# other.net
KiCad netlist of a schematic drawn in Altium Designer
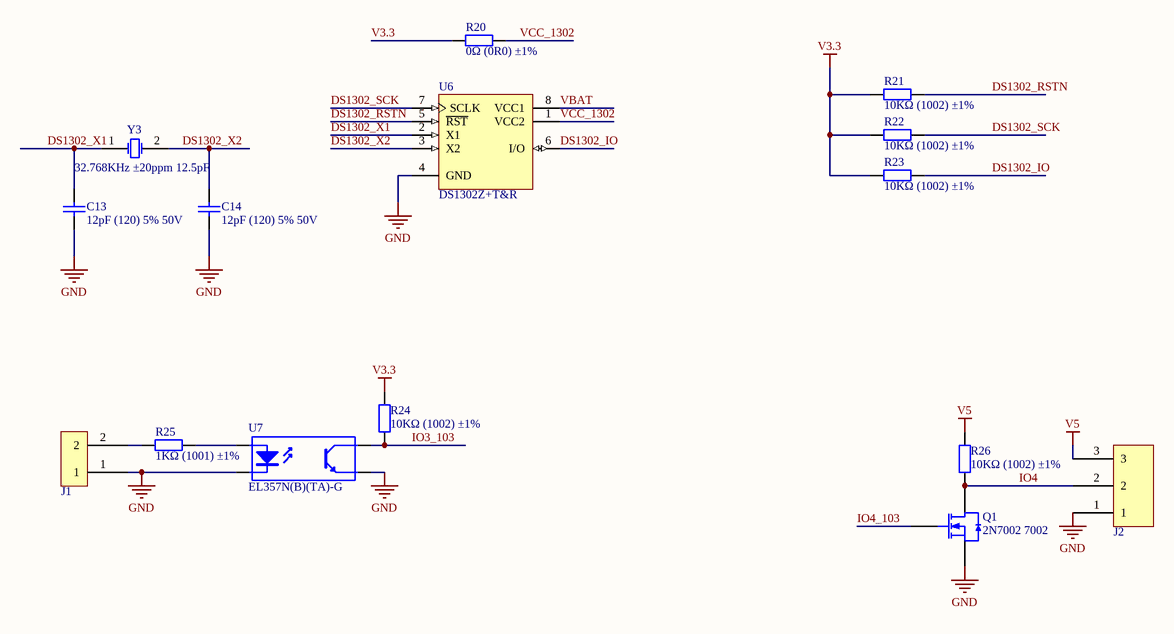
[diagram p0: other.SchDoc]

(export (version "E")
  (design (tool "Eeschema 10.0.6"))
  (components
    (comp (ref "C13")
      (value "12pF (120) 5% 50V")
      (footprint "0603_C")
      (description "贴片电容")
      (libsource (lib "Miscellaneous Devices LC") (part "0603 12pF (120) 5% 50V"))
    )
    (comp (ref "C14")
      (value "12pF (120) 5% 50V")
      (footprint "0603_C")
      (description "贴片电容")
      (libsource (lib "Miscellaneous Devices LC") (part "0603 12pF (120) 5% 50V"))
    )
    (comp (ref "J1") (value "KF301-2P") (footprint "KF301-2P") (libsource (lib "CHK-I") (part "KF301-2P")))
    (comp (ref "J2") (value "KF301-3P") (footprint "KF301-3P") (libsource (lib "CHK-I") (part "KF301-3P")))
    (comp (ref "Q1")
      (value "2N7002 7002")
      (footprint "SOT-23(SOT-23-3)")
      (description "MOS(场效应管)")
      (libsource (lib "Miscellaneous Devices LC") (part "2N7002 7002"))
    )
    (comp (ref "R20")
      (value "0Ω (0R0) ±1%")
      (footprint "1206_R")
      (description "贴片电阻")
      (libsource (lib "Miscellaneous Devices LC") (part "1206 0Ω (0R0) 1%"))
    )
    (comp (ref "R21")
      (value "10KΩ (1002) ±1%")
      (footprint "0603_R")
      (description "贴片电阻")
      (libsource (lib "Miscellaneous Devices LC") (part "0603 10KΩ (1002) 1%"))
    )
    (comp (ref "R22")
      (value "10KΩ (1002) ±1%")
      (footprint "0603_R")
      (description "贴片电阻")
      (libsource (lib "Miscellaneous Devices LC") (part "0603 10KΩ (1002) 1%"))
    )
    (comp (ref "R23")
      (value "10KΩ (1002) ±1%")
      (footprint "0603_R")
      (description "贴片电阻")
      (libsource (lib "Miscellaneous Devices LC") (part "0603 10KΩ (1002) 1%"))
    )
    (comp (ref "R24")
      (value "10KΩ (1002) ±1%")
      (footprint "1206_R")
      (description "贴片电阻")
      (libsource (lib "Miscellaneous Devices LC") (part "1206 10KΩ (1002) 1%"))
    )
    (comp (ref "R25")
      (value "1KΩ (1001) ±1%")
      (footprint "1206_R")
      (description "贴片电阻")
      (libsource (lib "Miscellaneous Devices LC") (part "1206 1KΩ (1001) 1%"))
    )
    (comp (ref "R26")
      (value "10KΩ (1002) ±1%")
      (footprint "1206_R")
      (description "贴片电阻")
      (libsource (lib "Miscellaneous Devices LC") (part "1206 10KΩ (1002) 1%"))
    )
    (comp (ref "U6")
      (value "DS1302Z+T&R")
      (footprint "SOIC-8_150mil")
      (description "实时时钟")
      (libsource (lib "Miscellaneous Devices LC") (part "DS1302Z+T&R_[C8959]"))
    )
    (comp (ref "U7")
      (value "EL357N(B)(TA)-G")
      (footprint "SOP-4_P2.54")
      (description "贴片光耦")
      (libsource (lib "Miscellaneous Devices LC") (part "EL357N(B)(TA)-G_[C6649]"))
    )
    (comp (ref "Y3")
      (value "32.768KHz ±20ppm 12.5pF")
      (footprint "SMD-3215_2P FC - 135")
      (description "贴片晶振")
      (libsource (lib "Miscellaneous Devices LC") (part "SMD-3215_2P 32.768KHz 20ppm 12.5pF"))
    )
  )
  (nets
    (net (code "1") (name "/DS1302_IO") (class "Default")
      (node (ref "R23") (pin "2") (pinfunction "2_2") (pintype "passive"))
      (node (ref "U6") (pin "6") (pinfunction "I/O_6") (pintype "bidirectional"))
    )
    (net (code "2") (name "/DS1302_RSTN") (class "Default")
      (node (ref "R21") (pin "2") (pinfunction "2_2") (pintype "passive"))
      (node (ref "U6") (pin "5") (pinfunction "~{RST}_5") (pintype "input"))
    )
    (net (code "3") (name "/DS1302_SCK") (class "Default")
      (node (ref "R22") (pin "2") (pinfunction "2_2") (pintype "passive"))
      (node (ref "U6") (pin "7") (pinfunction "SCLK_7") (pintype "input"))
    )
    (net (code "4") (name "/DS1302_X1") (class "Default")
      (node (ref "C13") (pin "2") (pinfunction "2_2") (pintype "passive"))
      (node (ref "U6") (pin "2") (pinfunction "X1_2") (pintype "input"))
      (node (ref "Y3") (pin "1") (pinfunction "OSC1_1") (pintype "passive"))
    )
    (net (code "5") (name "/DS1302_X2") (class "Default")
      (node (ref "C14") (pin "2") (pinfunction "2_2") (pintype "passive"))
      (node (ref "U6") (pin "3") (pinfunction "X2_3") (pintype "input"))
      (node (ref "Y3") (pin "2") (pinfunction "OSC2_2") (pintype "passive"))
    )
    (net (code "6") (name "/IO3_103") (class "Default")
      (node (ref "R24") (pin "1") (pinfunction "1_1") (pintype "passive"))
      (node (ref "U7") (pin "4") (pinfunction "C_4") (pintype "passive"))
    )
    (net (code "7") (name "/IO4") (class "Default")
      (node (ref "J2") (pin "2") (pinfunction "2_2") (pintype "passive"))
      (node (ref "Q1") (pin "3") (pinfunction "D_3") (pintype "passive"))
      (node (ref "R26") (pin "1") (pinfunction "1_1") (pintype "passive"))
    )
    (net (code "8") (name "/IO4_103") (class "Default")
      (node (ref "Q1") (pin "1") (pinfunction "G_1") (pintype "passive"))
    )
    (net (code "9") (name "/VBAT") (class "Default")
      (node (ref "U6") (pin "8") (pinfunction "VCC1_8") (pintype "power_in"))
    )
    (net (code "10") (name "/VCC_1302") (class "Default")
      (node (ref "R20") (pin "2") (pinfunction "2_2") (pintype "passive"))
      (node (ref "U6") (pin "1") (pinfunction "VCC2_1") (pintype "power_in"))
    )
    (net (code "11") (name "GND") (class "Default")
      (node (ref "C13") (pin "1") (pinfunction "1_1") (pintype "passive"))
      (node (ref "C14") (pin "1") (pinfunction "1_1") (pintype "passive"))
      (node (ref "J1") (pin "1") (pinfunction "1_1") (pintype "passive"))
      (node (ref "J2") (pin "1") (pinfunction "1_1") (pintype "passive"))
      (node (ref "Q1") (pin "2") (pinfunction "S_2") (pintype "passive"))
      (node (ref "U6") (pin "4") (pinfunction "GND_4") (pintype "power_in"))
      (node (ref "U7") (pin "2") (pinfunction "K_2") (pintype "passive"))
      (node (ref "U7") (pin "3") (pinfunction "E_3") (pintype "passive"))
    )
    (net (code "12") (name "Net-(J1-Pad2)") (class "Default")
      (node (ref "J1") (pin "2") (pinfunction "2_2") (pintype "passive"))
      (node (ref "R25") (pin "1") (pinfunction "1_1") (pintype "passive"))
    )
    (net (code "13") (name "Net-(U7-A)") (class "Default")
      (node (ref "R25") (pin "2") (pinfunction "2_2") (pintype "passive"))
      (node (ref "U7") (pin "1") (pinfunction "A_1") (pintype "passive"))
    )
    (net (code "14") (name "V3.3") (class "Default")
      (node (ref "R20") (pin "1") (pinfunction "1_1") (pintype "passive"))
      (node (ref "R21") (pin "1") (pinfunction "1_1") (pintype "passive"))
      (node (ref "R22") (pin "1") (pinfunction "1_1") (pintype "passive"))
      (node (ref "R23") (pin "1") (pinfunction "1_1") (pintype "passive"))
      (node (ref "R24") (pin "2") (pinfunction "2_2") (pintype "passive"))
    )
    (net (code "15") (name "V5") (class "Default")
      (node (ref "J2") (pin "3") (pinfunction "3_3") (pintype "passive"))
      (node (ref "R26") (pin "2") (pinfunction "2_2") (pintype "passive"))
    )
  )
)
